# driver.net
KiCad netlist of a schematic drawn in Altium Designer
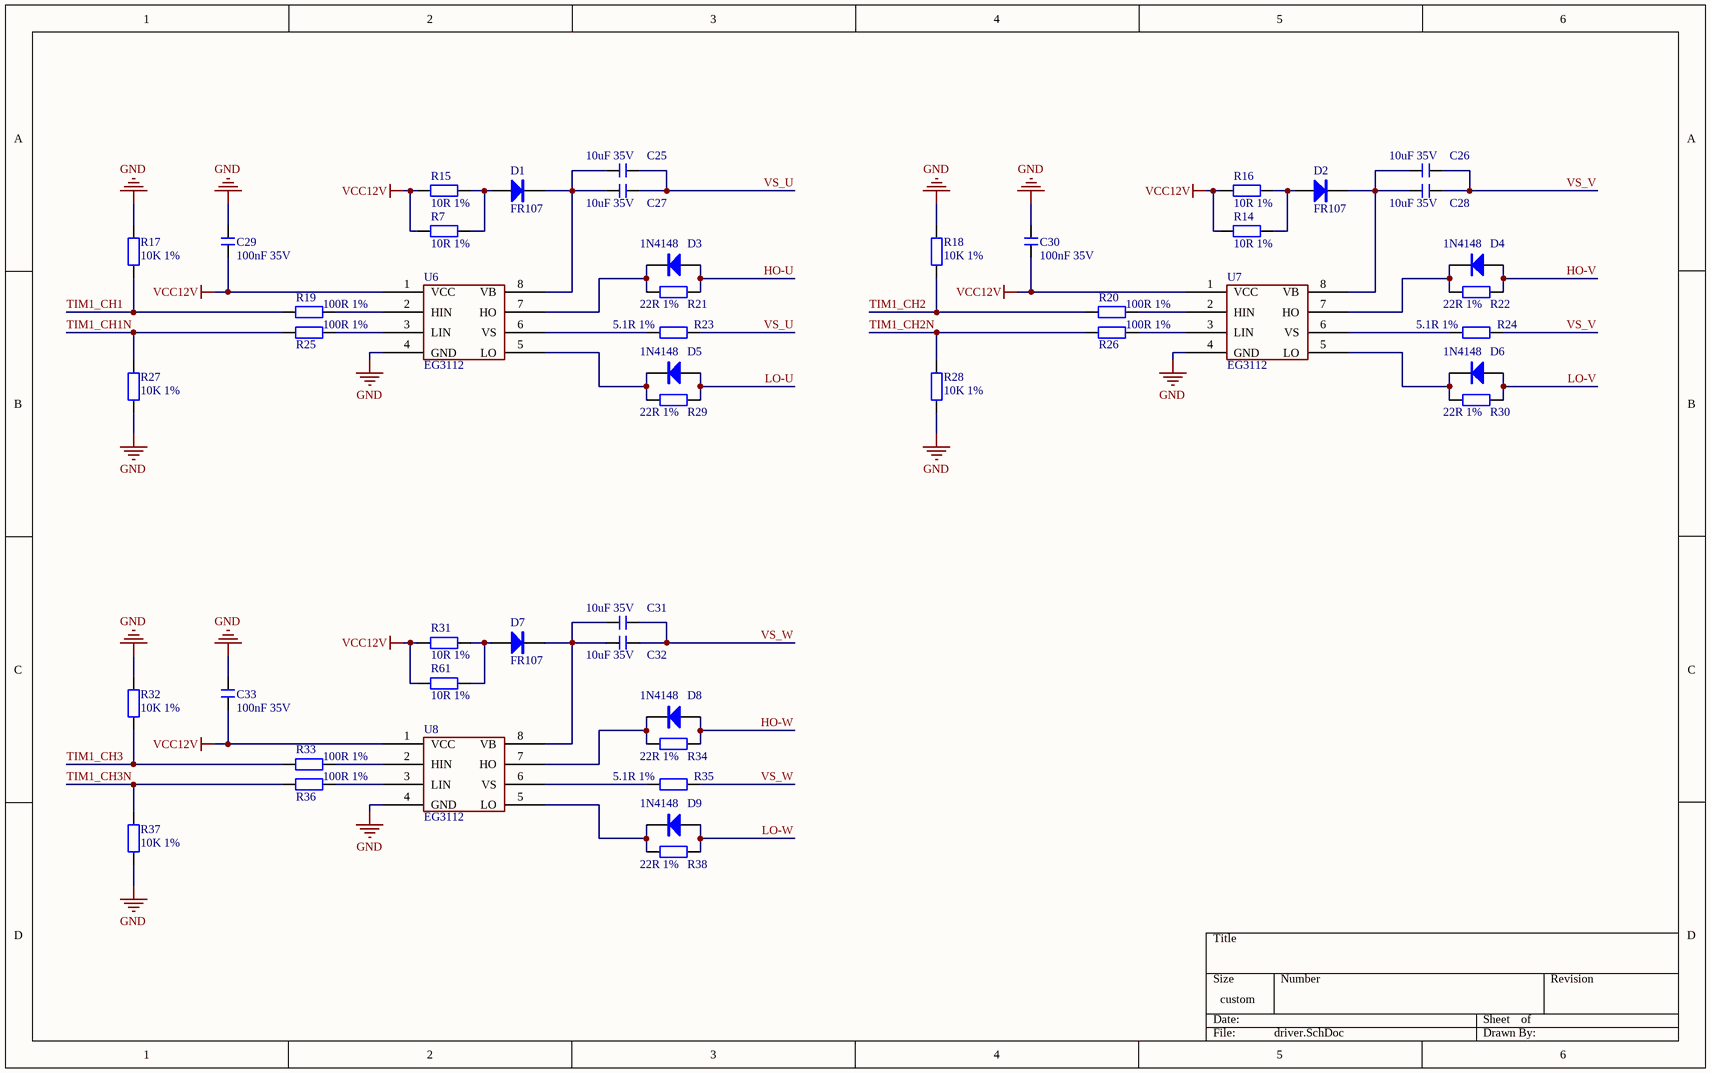
[diagram p0: driver.SchDoc]

(export (version "E")
  (design (tool "Eeschema 10.0.6"))
  (components
    (comp (ref "C25")
      (value "10uF 35V")
      (footprint "C1206_L")
      (description "无极性贴片电容")
      (fields (field (name "版权归属") "源创客"))
      (libsource (lib "Capacitor") (part "C"))
    )
    (comp (ref "C26")
      (value "10uF 35V")
      (footprint "C1206_L")
      (description "无极性贴片电容")
      (fields (field (name "版权归属") "源创客"))
      (libsource (lib "Capacitor") (part "C"))
    )
    (comp (ref "C27")
      (value "10uF 35V")
      (footprint "C1206_L")
      (description "无极性贴片电容")
      (fields (field (name "版权归属") "源创客"))
      (libsource (lib "Capacitor") (part "C"))
    )
    (comp (ref "C28")
      (value "10uF 35V")
      (footprint "C1206_L")
      (description "无极性贴片电容")
      (fields (field (name "版权归属") "源创客"))
      (libsource (lib "Capacitor") (part "C"))
    )
    (comp (ref "C29")
      (value "100nF 35V")
      (footprint "C0603_L")
      (description "无极性贴片电容")
      (fields (field (name "版权归属") "源创客"))
      (libsource (lib "Capacitor") (part "C"))
    )
    (comp (ref "C30")
      (value "100nF 35V")
      (footprint "C0603_L")
      (description "无极性贴片电容")
      (fields (field (name "版权归属") "源创客"))
      (libsource (lib "Capacitor") (part "C"))
    )
    (comp (ref "C31")
      (value "10uF 35V")
      (footprint "C1206_L")
      (description "无极性贴片电容")
      (fields (field (name "版权归属") "源创客"))
      (libsource (lib "Capacitor") (part "C"))
    )
    (comp (ref "C32")
      (value "10uF 35V")
      (footprint "C1206_L")
      (description "无极性贴片电容")
      (fields (field (name "版权归属") "源创客"))
      (libsource (lib "Capacitor") (part "C"))
    )
    (comp (ref "C33")
      (value "100nF 35V")
      (footprint "C0603_L")
      (description "无极性贴片电容")
      (fields (field (name "版权归属") "源创客"))
      (libsource (lib "Capacitor") (part "C"))
    )
    (comp (ref "D1")
      (value "FR107")
      (footprint "SOD-123")
      (description "快恢复整流二极管")
      (fields (field (name "版权归属") "源创客"))
      (libsource (lib "Diode") (part "FR107"))
    )
    (comp (ref "D2")
      (value "FR107")
      (footprint "SOD-123")
      (description "快恢复整流二极管")
      (fields (field (name "版权归属") "源创客"))
      (libsource (lib "Diode") (part "FR107"))
    )
    (comp (ref "D3")
      (value "1N4148")
      (footprint "SOD-323")
      (description "高速开关二极管")
      (fields (field (name "版权归属") "源创客"))
      (libsource (lib "Diode") (part "1N4148"))
    )
    (comp (ref "D4")
      (value "1N4148")
      (footprint "SOD-323")
      (description "高速开关二极管")
      (fields (field (name "版权归属") "源创客"))
      (libsource (lib "Diode") (part "1N4148"))
    )
    (comp (ref "D5")
      (value "1N4148")
      (footprint "SOD-323")
      (description "高速开关二极管")
      (fields (field (name "版权归属") "源创客"))
      (libsource (lib "Diode") (part "1N4148"))
    )
    (comp (ref "D6")
      (value "1N4148")
      (footprint "SOD-323")
      (description "高速开关二极管")
      (fields (field (name "版权归属") "源创客"))
      (libsource (lib "Diode") (part "1N4148"))
    )
    (comp (ref "D7")
      (value "FR107")
      (footprint "SOD-123")
      (description "快恢复整流二极管")
      (fields (field (name "版权归属") "源创客"))
      (libsource (lib "Diode") (part "FR107"))
    )
    (comp (ref "D8")
      (value "1N4148")
      (footprint "SOD-323")
      (description "高速开关二极管")
      (fields (field (name "版权归属") "源创客"))
      (libsource (lib "Diode") (part "1N4148"))
    )
    (comp (ref "D9")
      (value "1N4148")
      (footprint "SOD-323")
      (description "高速开关二极管")
      (fields (field (name "版权归属") "源创客"))
      (libsource (lib "Diode") (part "1N4148"))
    )
    (comp (ref "R7")
      (value "10R 1%")
      (footprint "R0603_l")
      (description "贴片电阻")
      (fields (field (name "版权归属") "源创客"))
      (libsource (lib "Resistor") (part "R"))
    )
    (comp (ref "R14")
      (value "10R 1%")
      (footprint "R0603_l")
      (description "贴片电阻")
      (fields (field (name "版权归属") "源创客"))
      (libsource (lib "Resistor") (part "R"))
    )
    (comp (ref "R15")
      (value "10R 1%")
      (footprint "R0603_l")
      (description "贴片电阻")
      (fields (field (name "版权归属") "源创客"))
      (libsource (lib "Resistor") (part "R"))
    )
    (comp (ref "R16")
      (value "10R 1%")
      (footprint "R0603_l")
      (description "贴片电阻")
      (fields (field (name "版权归属") "源创客"))
      (libsource (lib "Resistor") (part "R"))
    )
    (comp (ref "R17")
      (value "10K 1%")
      (footprint "R0603_l")
      (description "贴片电阻")
      (fields (field (name "版权归属") "源创客"))
      (libsource (lib "Resistor") (part "R"))
    )
    (comp (ref "R18")
      (value "10K 1%")
      (footprint "R0603_l")
      (description "贴片电阻")
      (fields (field (name "版权归属") "源创客"))
      (libsource (lib "Resistor") (part "R"))
    )
    (comp (ref "R19")
      (value "100R 1%")
      (footprint "R0603_l")
      (description "贴片电阻")
      (fields (field (name "版权归属") "源创客"))
      (libsource (lib "Resistor") (part "R"))
    )
    (comp (ref "R20")
      (value "100R 1%")
      (footprint "R0603_l")
      (description "贴片电阻")
      (fields (field (name "版权归属") "源创客"))
      (libsource (lib "Resistor") (part "R"))
    )
    (comp (ref "R21")
      (value "22R 1%")
      (footprint "R0603_l")
      (description "贴片电阻")
      (fields (field (name "版权归属") "源创客"))
      (libsource (lib "Resistor") (part "R"))
    )
    (comp (ref "R22")
      (value "22R 1%")
      (footprint "R0603_l")
      (description "贴片电阻")
      (fields (field (name "版权归属") "源创客"))
      (libsource (lib "Resistor") (part "R"))
    )
    (comp (ref "R23")
      (value "5.1R 1%")
      (footprint "R0603_l")
      (description "贴片电阻")
      (fields (field (name "版权归属") "源创客"))
      (libsource (lib "Resistor") (part "R"))
    )
    (comp (ref "R24")
      (value "5.1R 1%")
      (footprint "R0603_l")
      (description "贴片电阻")
      (fields (field (name "版权归属") "源创客"))
      (libsource (lib "Resistor") (part "R"))
    )
    (comp (ref "R25")
      (value "100R 1%")
      (footprint "R0603_l")
      (description "贴片电阻")
      (fields (field (name "版权归属") "源创客"))
      (libsource (lib "Resistor") (part "R"))
    )
    (comp (ref "R26")
      (value "100R 1%")
      (footprint "R0603_l")
      (description "贴片电阻")
      (fields (field (name "版权归属") "源创客"))
      (libsource (lib "Resistor") (part "R"))
    )
    (comp (ref "R27")
      (value "10K 1%")
      (footprint "R0603_l")
      (description "贴片电阻")
      (fields (field (name "版权归属") "源创客"))
      (libsource (lib "Resistor") (part "R"))
    )
    (comp (ref "R28")
      (value "10K 1%")
      (footprint "R0603_l")
      (description "贴片电阻")
      (fields (field (name "版权归属") "源创客"))
      (libsource (lib "Resistor") (part "R"))
    )
    (comp (ref "R29")
      (value "22R 1%")
      (footprint "R0603_l")
      (description "贴片电阻")
      (fields (field (name "版权归属") "源创客"))
      (libsource (lib "Resistor") (part "R"))
    )
    (comp (ref "R30")
      (value "22R 1%")
      (footprint "R0603_l")
      (description "贴片电阻")
      (fields (field (name "版权归属") "源创客"))
      (libsource (lib "Resistor") (part "R"))
    )
    (comp (ref "R31")
      (value "10R 1%")
      (footprint "R0603_l")
      (description "贴片电阻")
      (fields (field (name "版权归属") "源创客"))
      (libsource (lib "Resistor") (part "R"))
    )
    (comp (ref "R32")
      (value "10K 1%")
      (footprint "R0603_l")
      (description "贴片电阻")
      (fields (field (name "版权归属") "源创客"))
      (libsource (lib "Resistor") (part "R"))
    )
    (comp (ref "R33")
      (value "100R 1%")
      (footprint "R0603_l")
      (description "贴片电阻")
      (fields (field (name "版权归属") "源创客"))
      (libsource (lib "Resistor") (part "R"))
    )
    (comp (ref "R34")
      (value "22R 1%")
      (footprint "R0603_l")
      (description "贴片电阻")
      (fields (field (name "版权归属") "源创客"))
      (libsource (lib "Resistor") (part "R"))
    )
    (comp (ref "R35")
      (value "5.1R 1%")
      (footprint "R0603_l")
      (description "贴片电阻")
      (fields (field (name "版权归属") "源创客"))
      (libsource (lib "Resistor") (part "R"))
    )
    (comp (ref "R36")
      (value "100R 1%")
      (footprint "R0603_l")
      (description "贴片电阻")
      (fields (field (name "版权归属") "源创客"))
      (libsource (lib "Resistor") (part "R"))
    )
    (comp (ref "R37")
      (value "10K 1%")
      (footprint "R0603_l")
      (description "贴片电阻")
      (fields (field (name "版权归属") "源创客"))
      (libsource (lib "Resistor") (part "R"))
    )
    (comp (ref "R38")
      (value "22R 1%")
      (footprint "R0603_l")
      (description "贴片电阻")
      (fields (field (name "版权归属") "源创客"))
      (libsource (lib "Resistor") (part "R"))
    )
    (comp (ref "R61")
      (value "10R 1%")
      (footprint "R0603_l")
      (description "贴片电阻")
      (fields (field (name "版权归属") "源创客"))
      (libsource (lib "Resistor") (part "R"))
    )
    (comp (ref "U6")
      (value "EG3112")
      (footprint "SOP-8")
      (description "栅极驱动")
      (libsource (lib "栅极驱动") (part "EG3113"))
    )
    (comp (ref "U7")
      (value "EG3112")
      (footprint "SOP-8")
      (description "栅极驱动")
      (libsource (lib "栅极驱动") (part "EG3113"))
    )
    (comp (ref "U8")
      (value "EG3112")
      (footprint "SOP-8")
      (description "栅极驱动")
      (libsource (lib "栅极驱动") (part "EG3113"))
    )
  )
  (nets
    (net (code "1") (name "/HO-U") (class "Default")
      (node (ref "D3") (pin "1") (pinfunction "A_1") (pintype "passive"))
      (node (ref "R21") (pin "2") (pinfunction "2_2") (pintype "passive"))
    )
    (net (code "2") (name "/HO-V") (class "Default")
      (node (ref "D4") (pin "1") (pinfunction "A_1") (pintype "passive"))
      (node (ref "R22") (pin "2") (pinfunction "2_2") (pintype "passive"))
    )
    (net (code "3") (name "/HO-W") (class "Default")
      (node (ref "D8") (pin "1") (pinfunction "A_1") (pintype "passive"))
      (node (ref "R34") (pin "2") (pinfunction "2_2") (pintype "passive"))
    )
    (net (code "4") (name "/LO-U") (class "Default")
      (node (ref "D5") (pin "1") (pinfunction "A_1") (pintype "passive"))
      (node (ref "R29") (pin "2") (pinfunction "2_2") (pintype "passive"))
    )
    (net (code "5") (name "/LO-V") (class "Default")
      (node (ref "D6") (pin "1") (pinfunction "A_1") (pintype "passive"))
      (node (ref "R30") (pin "2") (pinfunction "2_2") (pintype "passive"))
    )
    (net (code "6") (name "/LO-W") (class "Default")
      (node (ref "D9") (pin "1") (pinfunction "A_1") (pintype "passive"))
      (node (ref "R38") (pin "2") (pinfunction "2_2") (pintype "passive"))
    )
    (net (code "7") (name "/TIM1_CH1") (class "Default")
      (node (ref "R17") (pin "1") (pinfunction "1_1") (pintype "passive"))
      (node (ref "R19") (pin "1") (pinfunction "1_1") (pintype "passive"))
    )
    (net (code "8") (name "/TIM1_CH1N") (class "Default")
      (node (ref "R25") (pin "1") (pinfunction "1_1") (pintype "passive"))
      (node (ref "R27") (pin "2") (pinfunction "2_2") (pintype "passive"))
    )
    (net (code "9") (name "/TIM1_CH2") (class "Default")
      (node (ref "R18") (pin "1") (pinfunction "1_1") (pintype "passive"))
      (node (ref "R20") (pin "1") (pinfunction "1_1") (pintype "passive"))
    )
    (net (code "10") (name "/TIM1_CH2N") (class "Default")
      (node (ref "R26") (pin "1") (pinfunction "1_1") (pintype "passive"))
      (node (ref "R28") (pin "2") (pinfunction "2_2") (pintype "passive"))
    )
    (net (code "11") (name "/TIM1_CH3") (class "Default")
      (node (ref "R32") (pin "1") (pinfunction "1_1") (pintype "passive"))
      (node (ref "R33") (pin "1") (pinfunction "1_1") (pintype "passive"))
    )
    (net (code "12") (name "/TIM1_CH3N") (class "Default")
      (node (ref "R36") (pin "1") (pinfunction "1_1") (pintype "passive"))
      (node (ref "R37") (pin "2") (pinfunction "2_2") (pintype "passive"))
    )
    (net (code "13") (name "/VS_U") (class "Default")
      (node (ref "C25") (pin "1") (pinfunction "1_1") (pintype "passive"))
      (node (ref "C27") (pin "1") (pinfunction "1_1") (pintype "passive"))
      (node (ref "R23") (pin "2") (pinfunction "2_2") (pintype "passive"))
    )
    (net (code "14") (name "/VS_V") (class "Default")
      (node (ref "C26") (pin "1") (pinfunction "1_1") (pintype "passive"))
      (node (ref "C28") (pin "1") (pinfunction "1_1") (pintype "passive"))
      (node (ref "R24") (pin "2") (pinfunction "2_2") (pintype "passive"))
    )
    (net (code "15") (name "/VS_W") (class "Default")
      (node (ref "C31") (pin "1") (pinfunction "1_1") (pintype "passive"))
      (node (ref "C32") (pin "1") (pinfunction "1_1") (pintype "passive"))
      (node (ref "R35") (pin "2") (pinfunction "2_2") (pintype "passive"))
    )
    (net (code "16") (name "GND") (class "Default")
      (node (ref "C29") (pin "1") (pinfunction "1_1") (pintype "passive"))
      (node (ref "C30") (pin "1") (pinfunction "1_1") (pintype "passive"))
      (node (ref "C33") (pin "1") (pinfunction "1_1") (pintype "passive"))
      (node (ref "R17") (pin "2") (pinfunction "2_2") (pintype "passive"))
      (node (ref "R18") (pin "2") (pinfunction "2_2") (pintype "passive"))
      (node (ref "R27") (pin "1") (pinfunction "1_1") (pintype "passive"))
      (node (ref "R28") (pin "1") (pinfunction "1_1") (pintype "passive"))
      (node (ref "R32") (pin "2") (pinfunction "2_2") (pintype "passive"))
      (node (ref "R37") (pin "1") (pinfunction "1_1") (pintype "passive"))
      (node (ref "U6") (pin "4") (pinfunction "GND_4") (pintype "passive"))
      (node (ref "U7") (pin "4") (pinfunction "GND_4") (pintype "passive"))
      (node (ref "U8") (pin "4") (pinfunction "GND_4") (pintype "passive"))
    )
    (net (code "17") (name "Net-(D1-A)") (class "Default")
      (node (ref "D1") (pin "1") (pinfunction "A_1") (pintype "passive"))
      (node (ref "R15") (pin "2") (pinfunction "2_2") (pintype "passive"))
      (node (ref "R7") (pin "2") (pinfunction "2_2") (pintype "passive"))
    )
    (net (code "18") (name "Net-(D1-K)") (class "Default")
      (node (ref "C25") (pin "2") (pinfunction "2_2") (pintype "passive"))
      (node (ref "C27") (pin "2") (pinfunction "2_2") (pintype "passive"))
      (node (ref "D1") (pin "2") (pinfunction "K_2") (pintype "passive"))
      (node (ref "U6") (pin "8") (pinfunction "VB_8") (pintype "passive"))
    )
    (net (code "19") (name "Net-(D2-A)") (class "Default")
      (node (ref "D2") (pin "1") (pinfunction "A_1") (pintype "passive"))
      (node (ref "R14") (pin "2") (pinfunction "2_2") (pintype "passive"))
      (node (ref "R16") (pin "2") (pinfunction "2_2") (pintype "passive"))
    )
    (net (code "20") (name "Net-(D2-K)") (class "Default")
      (node (ref "C26") (pin "2") (pinfunction "2_2") (pintype "passive"))
      (node (ref "C28") (pin "2") (pinfunction "2_2") (pintype "passive"))
      (node (ref "D2") (pin "2") (pinfunction "K_2") (pintype "passive"))
      (node (ref "U7") (pin "8") (pinfunction "VB_8") (pintype "passive"))
    )
    (net (code "21") (name "Net-(D3-K)") (class "Default")
      (node (ref "D3") (pin "2") (pinfunction "K_2") (pintype "passive"))
      (node (ref "R21") (pin "1") (pinfunction "1_1") (pintype "passive"))
      (node (ref "U6") (pin "7") (pinfunction "HO_7") (pintype "passive"))
    )
    (net (code "22") (name "Net-(D4-K)") (class "Default")
      (node (ref "D4") (pin "2") (pinfunction "K_2") (pintype "passive"))
      (node (ref "R22") (pin "1") (pinfunction "1_1") (pintype "passive"))
      (node (ref "U7") (pin "7") (pinfunction "HO_7") (pintype "passive"))
    )
    (net (code "23") (name "Net-(D5-K)") (class "Default")
      (node (ref "D5") (pin "2") (pinfunction "K_2") (pintype "passive"))
      (node (ref "R29") (pin "1") (pinfunction "1_1") (pintype "passive"))
      (node (ref "U6") (pin "5") (pinfunction "LO_5") (pintype "passive"))
    )
    (net (code "24") (name "Net-(D6-K)") (class "Default")
      (node (ref "D6") (pin "2") (pinfunction "K_2") (pintype "passive"))
      (node (ref "R30") (pin "1") (pinfunction "1_1") (pintype "passive"))
      (node (ref "U7") (pin "5") (pinfunction "LO_5") (pintype "passive"))
    )
    (net (code "25") (name "Net-(D7-A)") (class "Default")
      (node (ref "D7") (pin "1") (pinfunction "A_1") (pintype "passive"))
      (node (ref "R31") (pin "2") (pinfunction "2_2") (pintype "passive"))
      (node (ref "R61") (pin "2") (pinfunction "2_2") (pintype "passive"))
    )
    (net (code "26") (name "Net-(D7-K)") (class "Default")
      (node (ref "C31") (pin "2") (pinfunction "2_2") (pintype "passive"))
      (node (ref "C32") (pin "2") (pinfunction "2_2") (pintype "passive"))
      (node (ref "D7") (pin "2") (pinfunction "K_2") (pintype "passive"))
      (node (ref "U8") (pin "8") (pinfunction "VB_8") (pintype "passive"))
    )
    (net (code "27") (name "Net-(D8-K)") (class "Default")
      (node (ref "D8") (pin "2") (pinfunction "K_2") (pintype "passive"))
      (node (ref "R34") (pin "1") (pinfunction "1_1") (pintype "passive"))
      (node (ref "U8") (pin "7") (pinfunction "HO_7") (pintype "passive"))
    )
    (net (code "28") (name "Net-(D9-K)") (class "Default")
      (node (ref "D9") (pin "2") (pinfunction "K_2") (pintype "passive"))
      (node (ref "R38") (pin "1") (pinfunction "1_1") (pintype "passive"))
      (node (ref "U8") (pin "5") (pinfunction "LO_5") (pintype "passive"))
    )
    (net (code "29") (name "Net-(U6-HIN)") (class "Default")
      (node (ref "R19") (pin "2") (pinfunction "2_2") (pintype "passive"))
      (node (ref "U6") (pin "2") (pinfunction "HIN_2") (pintype "passive"))
    )
    (net (code "30") (name "Net-(U6-LIN)") (class "Default")
      (node (ref "R25") (pin "2") (pinfunction "2_2") (pintype "passive"))
      (node (ref "U6") (pin "3") (pinfunction "LIN_3") (pintype "passive"))
    )
    (net (code "31") (name "Net-(U6-VS)") (class "Default")
      (node (ref "R23") (pin "1") (pinfunction "1_1") (pintype "passive"))
      (node (ref "U6") (pin "6") (pinfunction "VS_6") (pintype "passive"))
    )
    (net (code "32") (name "Net-(U7-HIN)") (class "Default")
      (node (ref "R20") (pin "2") (pinfunction "2_2") (pintype "passive"))
      (node (ref "U7") (pin "2") (pinfunction "HIN_2") (pintype "passive"))
    )
    (net (code "33") (name "Net-(U7-LIN)") (class "Default")
      (node (ref "R26") (pin "2") (pinfunction "2_2") (pintype "passive"))
      (node (ref "U7") (pin "3") (pinfunction "LIN_3") (pintype "passive"))
    )
    (net (code "34") (name "Net-(U7-VS)") (class "Default")
      (node (ref "R24") (pin "1") (pinfunction "1_1") (pintype "passive"))
      (node (ref "U7") (pin "6") (pinfunction "VS_6") (pintype "passive"))
    )
    (net (code "35") (name "Net-(U8-HIN)") (class "Default")
      (node (ref "R33") (pin "2") (pinfunction "2_2") (pintype "passive"))
      (node (ref "U8") (pin "2") (pinfunction "HIN_2") (pintype "passive"))
    )
    (net (code "36") (name "Net-(U8-LIN)") (class "Default")
      (node (ref "R36") (pin "2") (pinfunction "2_2") (pintype "passive"))
      (node (ref "U8") (pin "3") (pinfunction "LIN_3") (pintype "passive"))
    )
    (net (code "37") (name "Net-(U8-VS)") (class "Default")
      (node (ref "R35") (pin "1") (pinfunction "1_1") (pintype "passive"))
      (node (ref "U8") (pin "6") (pinfunction "VS_6") (pintype "passive"))
    )
    (net (code "38") (name "VCC12V") (class "Default")
      (node (ref "C29") (pin "2") (pinfunction "2_2") (pintype "passive"))
      (node (ref "C30") (pin "2") (pinfunction "2_2") (pintype "passive"))
      (node (ref "C33") (pin "2") (pinfunction "2_2") (pintype "passive"))
      (node (ref "R14") (pin "1") (pinfunction "1_1") (pintype "passive"))
      (node (ref "R15") (pin "1") (pinfunction "1_1") (pintype "passive"))
      (node (ref "R16") (pin "1") (pinfunction "1_1") (pintype "passive"))
      (node (ref "R31") (pin "1") (pinfunction "1_1") (pintype "passive"))
      (node (ref "R61") (pin "1") (pinfunction "1_1") (pintype "passive"))
      (node (ref "R7") (pin "1") (pinfunction "1_1") (pintype "passive"))
      (node (ref "U6") (pin "1") (pinfunction "VCC_1") (pintype "passive"))
      (node (ref "U7") (pin "1") (pinfunction "VCC_1") (pintype "passive"))
      (node (ref "U8") (pin "1") (pinfunction "VCC_1") (pintype "passive"))
    )
  )
)
